# MAM_GND_V3.net
KiCad netlist of a schematic drawn in EAGLE
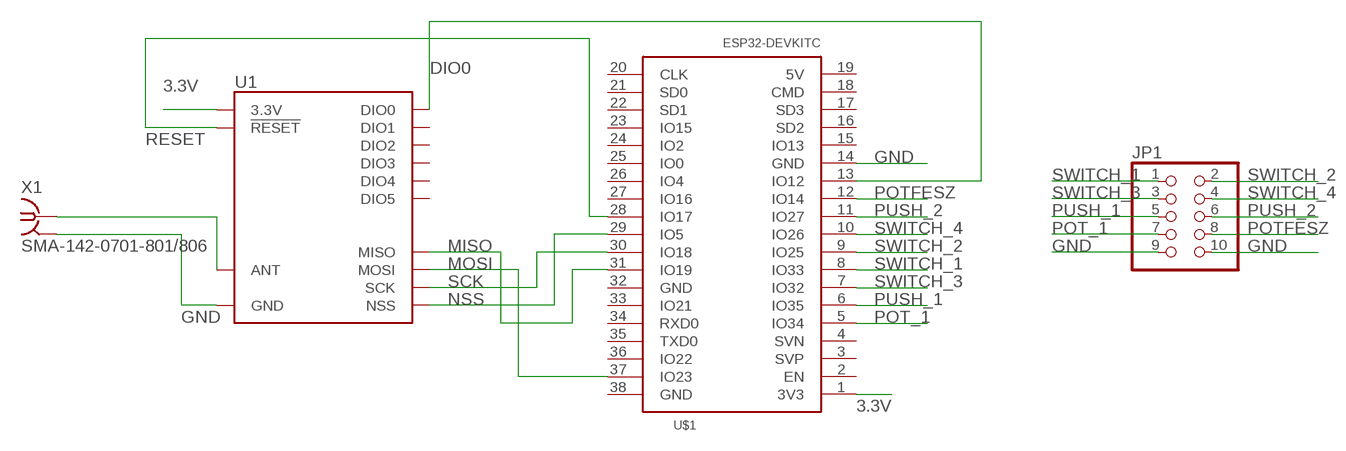
[diagram p0: schematic, sheet 1]

(export (version "E")
  (design (tool "Eeschema 10.0.6"))
  (components
    (comp (ref "JP1")
      (value "PINHD-2X5")
      (footprint "eagle-import:2X05")
      (libsource (lib "eagle-import") (part "PINHD-2X5"))
    )
    (comp (ref "U$1")
      (value "ESP32DEVKITC")
      (footprint "eagle-import:ESP32-DEVKITC")
      (libsource (lib "eagle-import") (part "ESP32DEVKITC"))
    )
    (comp (ref "U1")
      (value "RFM95W")
      (footprint "eagle-import:RFM95_96_97_98W")
      (libsource (lib "eagle-import") (part "RFM95W"))
    )
    (comp (ref "X1")
      (value "SMA-142-0701-801/806")
      (footprint "eagle-import:J502-ND-142-0701-801_806")
      (fields (field (name "MF") "JOHNSON COMPONENTS") (field (name "MPN") "142-0701-801"))
      (libsource (lib "eagle-import") (part "SMA-142-0701-801/806"))
    )
  )
  (nets
    (net (code "1") (name "/3.3V") (class "Default")
      (node (ref "U$1") (pin "1") (pinfunction "3V3_1") (pintype "bidirectional"))
      (node (ref "U1") (pin "3.3V") (pinfunction "3.3V_3.3V") (pintype "bidirectional"))
    )
    (net (code "2") (name "/DIO0") (class "Default")
      (node (ref "U$1") (pin "13") (pinfunction "IO12_13") (pintype "bidirectional"))
      (node (ref "U1") (pin "DIO0") (pinfunction "DIO0_DIO0") (pintype "bidirectional"))
    )
    (net (code "3") (name "/GND") (class "Default")
      (node (ref "JP1") (pin "10") (pinfunction "10_10") (pintype "passive"))
      (node (ref "JP1") (pin "9") (pinfunction "9_9") (pintype "passive"))
      (node (ref "U$1") (pin "14") (pinfunction "GND_14") (pintype "bidirectional"))
      (node (ref "U1") (pin "GND@1") (pinfunction "GND_GND@1") (pintype "bidirectional"))
      (node (ref "U1") (pin "GND@2") (pinfunction "GND_GND@2") (pintype "bidirectional"))
      (node (ref "U1") (pin "GND@3") (pinfunction "GND_GND@3") (pintype "bidirectional"))
      (node (ref "X1") (pin "G@1") (pinfunction "2_G@1") (pintype "passive"))
      (node (ref "X1") (pin "G@2") (pinfunction "2_G@2") (pintype "passive"))
      (node (ref "X1") (pin "G@3") (pinfunction "2_G@3") (pintype "passive"))
      (node (ref "X1") (pin "G@4") (pinfunction "2_G@4") (pintype "passive"))
    )
    (net (code "4") (name "/MISO") (class "Default")
      (node (ref "U$1") (pin "31") (pinfunction "IO19_31") (pintype "bidirectional"))
      (node (ref "U1") (pin "MISO") (pinfunction "MISO_MISO") (pintype "bidirectional"))
    )
    (net (code "5") (name "/MOSI") (class "Default")
      (node (ref "U$1") (pin "37") (pinfunction "IO23_37") (pintype "bidirectional"))
      (node (ref "U1") (pin "MOSI") (pinfunction "MOSI_MOSI") (pintype "bidirectional"))
    )
    (net (code "6") (name "/NSS") (class "Default")
      (node (ref "U$1") (pin "29") (pinfunction "IO5_29") (pintype "bidirectional"))
      (node (ref "U1") (pin "NSS") (pinfunction "NSS_NSS") (pintype "bidirectional"))
    )
    (net (code "7") (name "/POTFESZ") (class "Default")
      (node (ref "JP1") (pin "8") (pinfunction "8_8") (pintype "passive"))
      (node (ref "U$1") (pin "12") (pinfunction "IO14_12") (pintype "bidirectional"))
    )
    (net (code "8") (name "/POT_1") (class "Default")
      (node (ref "JP1") (pin "7") (pinfunction "7_7") (pintype "passive"))
      (node (ref "U$1") (pin "5") (pinfunction "IO34_5") (pintype "bidirectional"))
    )
    (net (code "9") (name "/PUSH_1") (class "Default")
      (node (ref "JP1") (pin "5") (pinfunction "5_5") (pintype "passive"))
      (node (ref "U$1") (pin "6") (pinfunction "IO35_6") (pintype "bidirectional"))
    )
    (net (code "10") (name "/PUSH_2") (class "Default")
      (node (ref "JP1") (pin "6") (pinfunction "6_6") (pintype "passive"))
      (node (ref "U$1") (pin "11") (pinfunction "IO27_11") (pintype "bidirectional"))
    )
    (net (code "11") (name "/RESET") (class "Default")
      (node (ref "U$1") (pin "28") (pinfunction "IO17_28") (pintype "bidirectional"))
      (node (ref "U1") (pin "!RESET") (pinfunction "~{RESET}_!RESET") (pintype "bidirectional"))
    )
    (net (code "12") (name "/SCK") (class "Default")
      (node (ref "U$1") (pin "30") (pinfunction "IO18_30") (pintype "bidirectional"))
      (node (ref "U1") (pin "SCK") (pinfunction "SCK_SCK") (pintype "bidirectional"))
    )
    (net (code "13") (name "/SWITCH_1") (class "Default")
      (node (ref "JP1") (pin "1") (pinfunction "1_1") (pintype "passive"))
      (node (ref "U$1") (pin "8") (pinfunction "IO33_8") (pintype "bidirectional"))
    )
    (net (code "14") (name "/SWITCH_2") (class "Default")
      (node (ref "JP1") (pin "2") (pinfunction "2_2") (pintype "passive"))
      (node (ref "U$1") (pin "9") (pinfunction "IO25_9") (pintype "bidirectional"))
    )
    (net (code "15") (name "/SWITCH_3") (class "Default")
      (node (ref "JP1") (pin "3") (pinfunction "3_3") (pintype "passive"))
      (node (ref "U$1") (pin "7") (pinfunction "IO32_7") (pintype "bidirectional"))
    )
    (net (code "16") (name "/SWITCH_4") (class "Default")
      (node (ref "JP1") (pin "4") (pinfunction "4_4") (pintype "passive"))
      (node (ref "U$1") (pin "10") (pinfunction "IO26_10") (pintype "bidirectional"))
    )
    (net (code "17") (name "Net-(U1-PadANT)") (class "Default")
      (node (ref "U1") (pin "ANT") (pinfunction "ANT_ANT") (pintype "bidirectional"))
      (node (ref "X1") (pin "1") (pinfunction "1_1") (pintype "passive"))
    )
    (net (code "18") (name "unconnected-(U$1-5V-Pad19)") (class "Default")
      (node (ref "U$1") (pin "19") (pinfunction "5V_19") (pintype "bidirectional"))
    )
    (net (code "19") (name "unconnected-(U$1-CLK-Pad20)") (class "Default")
      (node (ref "U$1") (pin "20") (pinfunction "CLK_20") (pintype "bidirectional"))
    )
    (net (code "20") (name "unconnected-(U$1-CMD-Pad18)") (class "Default")
      (node (ref "U$1") (pin "18") (pinfunction "CMD_18") (pintype "bidirectional"))
    )
    (net (code "21") (name "unconnected-(U$1-EN-Pad2)") (class "Default")
      (node (ref "U$1") (pin "2") (pinfunction "EN_2") (pintype "bidirectional"))
    )
    (net (code "22") (name "unconnected-(U$1-GND-Pad32)") (class "Default")
      (node (ref "U$1") (pin "32") (pinfunction "GND_32") (pintype "bidirectional"))
    )
    (net (code "23") (name "unconnected-(U$1-GND-Pad38)") (class "Default")
      (node (ref "U$1") (pin "38") (pinfunction "GND_38") (pintype "bidirectional"))
    )
    (net (code "24") (name "unconnected-(U$1-IO0-Pad25)") (class "Default")
      (node (ref "U$1") (pin "25") (pinfunction "IO0_25") (pintype "bidirectional"))
    )
    (net (code "25") (name "unconnected-(U$1-IO2-Pad24)") (class "Default")
      (node (ref "U$1") (pin "24") (pinfunction "IO2_24") (pintype "bidirectional"))
    )
    (net (code "26") (name "unconnected-(U$1-IO4-Pad26)") (class "Default")
      (node (ref "U$1") (pin "26") (pinfunction "IO4_26") (pintype "bidirectional"))
    )
    (net (code "27") (name "unconnected-(U$1-IO13-Pad15)") (class "Default")
      (node (ref "U$1") (pin "15") (pinfunction "IO13_15") (pintype "bidirectional"))
    )
    (net (code "28") (name "unconnected-(U$1-IO15-Pad23)") (class "Default")
      (node (ref "U$1") (pin "23") (pinfunction "IO15_23") (pintype "bidirectional"))
    )
    (net (code "29") (name "unconnected-(U$1-IO16-Pad27)") (class "Default")
      (node (ref "U$1") (pin "27") (pinfunction "IO16_27") (pintype "bidirectional"))
    )
    (net (code "30") (name "unconnected-(U$1-IO21-Pad33)") (class "Default")
      (node (ref "U$1") (pin "33") (pinfunction "IO21_33") (pintype "bidirectional"))
    )
    (net (code "31") (name "unconnected-(U$1-IO22-Pad36)") (class "Default")
      (node (ref "U$1") (pin "36") (pinfunction "IO22_36") (pintype "bidirectional"))
    )
    (net (code "32") (name "unconnected-(U$1-RXD0-Pad34)") (class "Default")
      (node (ref "U$1") (pin "34") (pinfunction "RXD0_34") (pintype "bidirectional"))
    )
    (net (code "33") (name "unconnected-(U$1-SD0-Pad21)") (class "Default")
      (node (ref "U$1") (pin "21") (pinfunction "SD0_21") (pintype "bidirectional"))
    )
    (net (code "34") (name "unconnected-(U$1-SD1-Pad22)") (class "Default")
      (node (ref "U$1") (pin "22") (pinfunction "SD1_22") (pintype "bidirectional"))
    )
    (net (code "35") (name "unconnected-(U$1-SD2-Pad16)") (class "Default")
      (node (ref "U$1") (pin "16") (pinfunction "SD2_16") (pintype "bidirectional"))
    )
    (net (code "36") (name "unconnected-(U$1-SD3-Pad17)") (class "Default")
      (node (ref "U$1") (pin "17") (pinfunction "SD3_17") (pintype "bidirectional"))
    )
    (net (code "37") (name "unconnected-(U$1-SVN-Pad4)") (class "Default")
      (node (ref "U$1") (pin "4") (pinfunction "SVN_4") (pintype "bidirectional"))
    )
    (net (code "38") (name "unconnected-(U$1-SVP-Pad3)") (class "Default")
      (node (ref "U$1") (pin "3") (pinfunction "SVP_3") (pintype "bidirectional"))
    )
    (net (code "39") (name "unconnected-(U$1-TXD0-Pad35)") (class "Default")
      (node (ref "U$1") (pin "35") (pinfunction "TXD0_35") (pintype "bidirectional"))
    )
    (net (code "40") (name "unconnected-(U1-PadDIO1)") (class "Default")
      (node (ref "U1") (pin "DIO1") (pinfunction "DIO1_DIO1") (pintype "bidirectional"))
    )
    (net (code "41") (name "unconnected-(U1-PadDIO2)") (class "Default")
      (node (ref "U1") (pin "DIO2") (pinfunction "DIO2_DIO2") (pintype "bidirectional"))
    )
    (net (code "42") (name "unconnected-(U1-PadDIO3)") (class "Default")
      (node (ref "U1") (pin "DIO3") (pinfunction "DIO3_DIO3") (pintype "bidirectional"))
    )
    (net (code "43") (name "unconnected-(U1-PadDIO4)") (class "Default")
      (node (ref "U1") (pin "DIO4") (pinfunction "DIO4_DIO4") (pintype "bidirectional"))
    )
    (net (code "44") (name "unconnected-(U1-PadDIO5)") (class "Default")
      (node (ref "U1") (pin "DIO5") (pinfunction "DIO5_DIO5") (pintype "bidirectional"))
    )
  )
)
